# Teensy_backpack.net
KiCad netlist of a schematic drawn in EAGLE
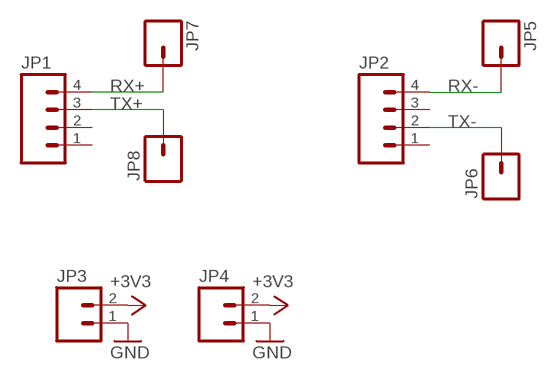
[diagram p0: schematic, sheet 1]

(export (version "E")
  (design (tool "Eeschema 10.0.6"))
  (components
    (comp (ref "JP1")
      (value "M04NO_SILK_ALL_ROUND")
      (footprint "eagle-import:1X04_NO_SILK_ALL_ROUND")
      (libsource (lib "eagle-import") (part "M04NO_SILK_ALL_ROUND"))
    )
    (comp (ref "JP2")
      (value "M04NO_SILK_ALL_ROUND")
      (footprint "eagle-import:1X04_NO_SILK_ALL_ROUND")
      (libsource (lib "eagle-import") (part "M04NO_SILK_ALL_ROUND"))
    )
    (comp (ref "JP3")
      (value "M021X02_NO_SILK")
      (footprint "eagle-import:1X02_NO_SILK")
      (libsource (lib "eagle-import") (part "M021X02_NO_SILK"))
    )
    (comp (ref "JP4")
      (value "M021X02_NO_SILK")
      (footprint "eagle-import:1X02_NO_SILK")
      (libsource (lib "eagle-import") (part "M021X02_NO_SILK"))
    )
    (comp (ref "JP5")
      (value "M01NOSILK-KIT")
      (footprint "eagle-import:1X01NS-KIT")
      (libsource (lib "eagle-import") (part "M01NOSILK-KIT"))
    )
    (comp (ref "JP6")
      (value "M01NOSILK-KIT")
      (footprint "eagle-import:1X01NS-KIT")
      (libsource (lib "eagle-import") (part "M01NOSILK-KIT"))
    )
    (comp (ref "JP7")
      (value "M01NOSILK-KIT")
      (footprint "eagle-import:1X01NS-KIT")
      (libsource (lib "eagle-import") (part "M01NOSILK-KIT"))
    )
    (comp (ref "JP8")
      (value "M01NOSILK-KIT")
      (footprint "eagle-import:1X01NS-KIT")
      (libsource (lib "eagle-import") (part "M01NOSILK-KIT"))
    )
  )
  (nets
    (net (code "1") (name "+3V3") (class "Default")
      (node (ref "JP3") (pin "2") (pinfunction "2_2") (pintype "passive"))
      (node (ref "JP4") (pin "2") (pinfunction "2_2") (pintype "passive"))
    )
    (net (code "2") (name "/RX+") (class "Default")
      (node (ref "JP1") (pin "4") (pinfunction "4_4") (pintype "passive"))
      (node (ref "JP7") (pin "1") (pinfunction "1_1") (pintype "passive"))
    )
    (net (code "3") (name "/RX-") (class "Default")
      (node (ref "JP2") (pin "4") (pinfunction "4_4") (pintype "passive"))
      (node (ref "JP5") (pin "1") (pinfunction "1_1") (pintype "passive"))
    )
    (net (code "4") (name "/TX+") (class "Default")
      (node (ref "JP1") (pin "3") (pinfunction "3_3") (pintype "passive"))
      (node (ref "JP8") (pin "1") (pinfunction "1_1") (pintype "passive"))
    )
    (net (code "5") (name "/TX-") (class "Default")
      (node (ref "JP2") (pin "2") (pinfunction "2_2") (pintype "passive"))
      (node (ref "JP6") (pin "1") (pinfunction "1_1") (pintype "passive"))
    )
    (net (code "6") (name "GND") (class "Default")
      (node (ref "JP3") (pin "1") (pinfunction "1_1") (pintype "passive"))
      (node (ref "JP4") (pin "1") (pinfunction "1_1") (pintype "passive"))
    )
    (net (code "7") (name "unconnected-(JP1-Pad1)") (class "Default")
      (node (ref "JP1") (pin "1") (pinfunction "1_1") (pintype "passive"))
    )
    (net (code "8") (name "unconnected-(JP1-Pad2)") (class "Default")
      (node (ref "JP1") (pin "2") (pinfunction "2_2") (pintype "passive"))
    )
    (net (code "9") (name "unconnected-(JP2-Pad1)") (class "Default")
      (node (ref "JP2") (pin "1") (pinfunction "1_1") (pintype "passive"))
    )
    (net (code "10") (name "unconnected-(JP2-Pad3)") (class "Default")
      (node (ref "JP2") (pin "3") (pinfunction "3_3") (pintype "passive"))
    )
  )
)
